# Sheet2.net
KiCad netlist of a schematic drawn in Altium Designer
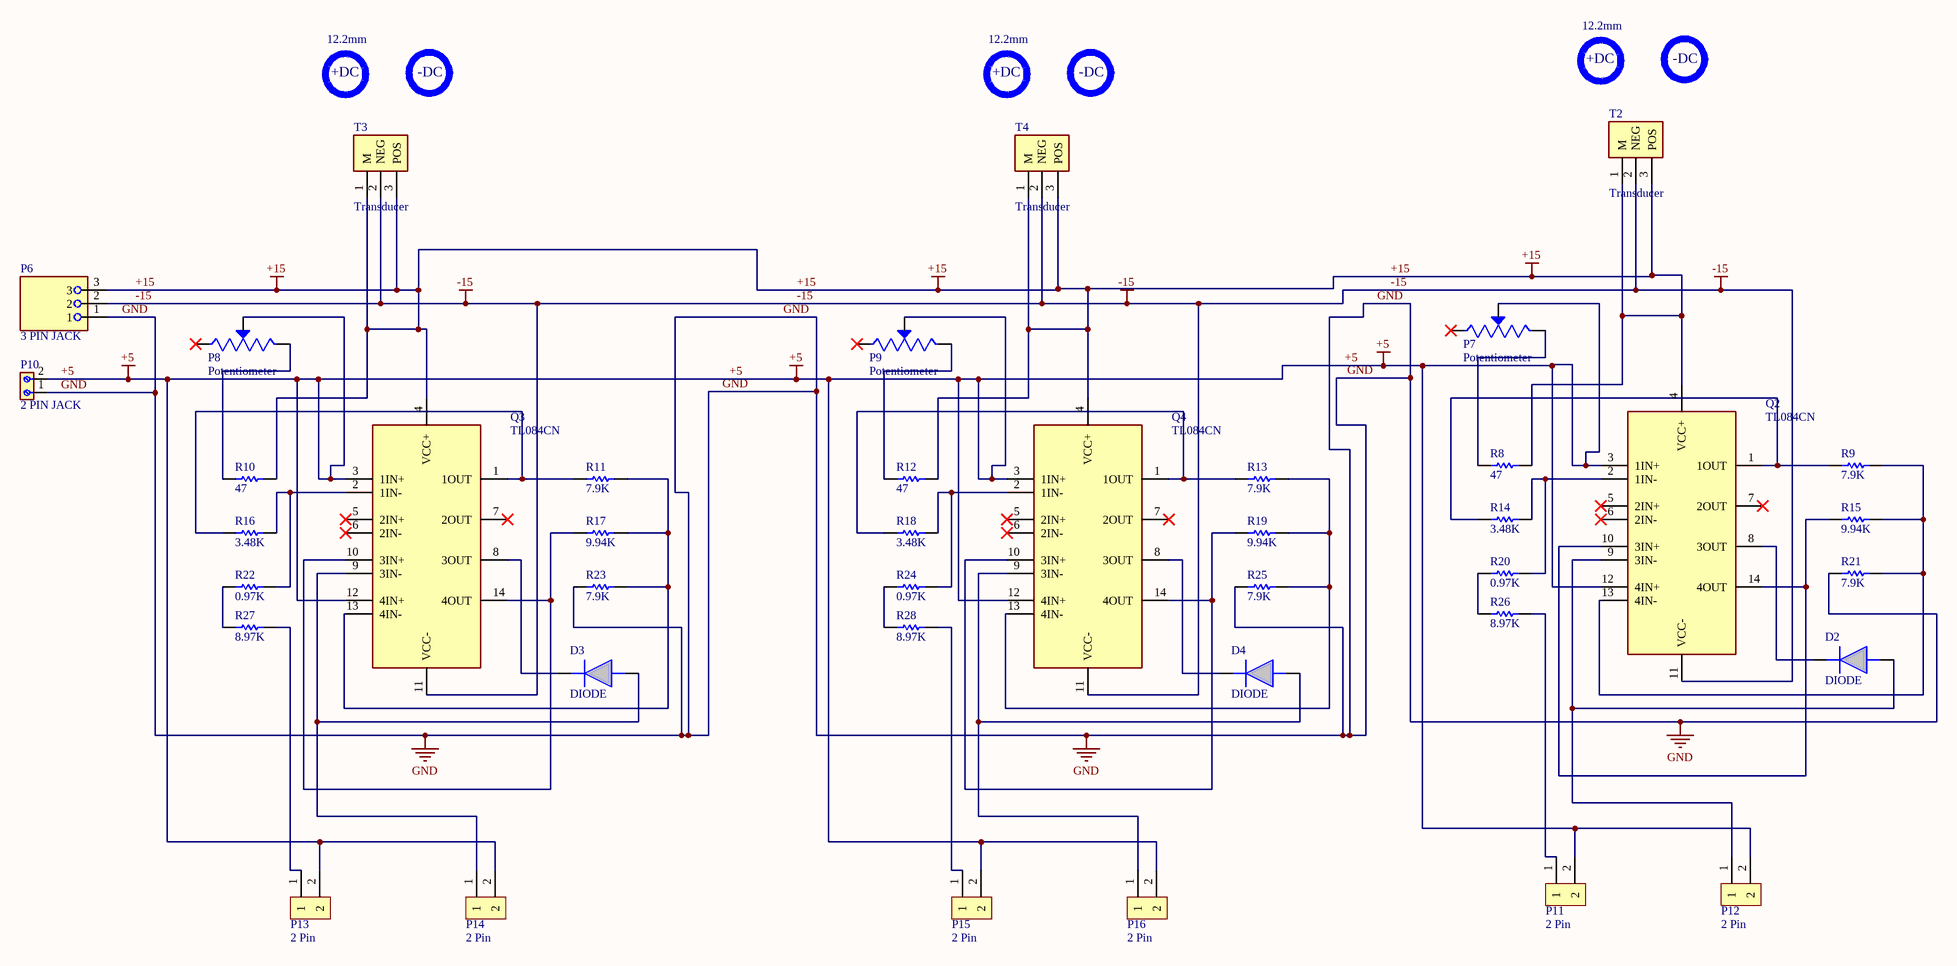
[diagram p0: Sheet2.SchDoc]

(export (version "E")
  (design (tool "Eeschema 10.0.6"))
  (components
    (comp (ref "D2")
      (value "DIODE")
      (footprint "Diode")
      (description "1N4007S")
      (libsource (lib "Schlib1") (part "DIODE"))
    )
    (comp (ref "D3")
      (value "DIODE")
      (footprint "Diode")
      (description "1N4007S")
      (libsource (lib "Schlib1") (part "DIODE"))
    )
    (comp (ref "D4")
      (value "DIODE")
      (footprint "Diode")
      (description "1N4007S")
      (libsource (lib "Schlib1") (part "DIODE"))
    )
    (comp (ref "P6")
      (value "3 PIN JACK")
      (footprint "3 PIN JACK")
      (libsource (lib "Schlib1") (part "3 PIN JACK"))
    )
    (comp (ref "P7")
      (value "Potentiometer")
      (footprint "Potentiometer")
      (libsource (lib "Schlib1") (part "Potentiometer"))
    )
    (comp (ref "P8")
      (value "Potentiometer")
      (footprint "Potentiometer")
      (libsource (lib "Schlib1") (part "Potentiometer"))
    )
    (comp (ref "P9")
      (value "Potentiometer")
      (footprint "Potentiometer")
      (libsource (lib "Schlib1") (part "Potentiometer"))
    )
    (comp (ref "P10")
      (value "2 PIN JACK")
      (footprint "2 PIN JACK")
      (libsource (lib "Schlib1") (part "2 PIN JACK"))
    )
    (comp (ref "P11")
      (value "2 Pin")
      (footprint "2 PIN")
      (description "22272021")
      (libsource (lib "Schlib1") (part "2 Pin"))
    )
    (comp (ref "P12")
      (value "2 Pin")
      (footprint "2 PIN")
      (description "22272021")
      (libsource (lib "Schlib1") (part "2 Pin"))
    )
    (comp (ref "P13")
      (value "2 Pin")
      (footprint "2 PIN")
      (description "22272021")
      (libsource (lib "Schlib1") (part "2 Pin"))
    )
    (comp (ref "P14")
      (value "2 Pin")
      (footprint "2 PIN")
      (description "22272021")
      (libsource (lib "Schlib1") (part "2 Pin"))
    )
    (comp (ref "P15")
      (value "2 Pin")
      (footprint "2 PIN")
      (description "22272021")
      (libsource (lib "Schlib1") (part "2 Pin"))
    )
    (comp (ref "P16")
      (value "2 Pin")
      (footprint "2 PIN")
      (description "22272021")
      (libsource (lib "Schlib1") (part "2 Pin"))
    )
    (comp (ref "Q2") (value "TL084CN") (footprint "TL084CN") (libsource (lib "Schlib1") (part "TL084CN")))
    (comp (ref "Q3") (value "TL084CN") (footprint "TL084CN") (libsource (lib "Schlib1") (part "TL084CN")))
    (comp (ref "Q4") (value "TL084CN") (footprint "TL084CN") (libsource (lib "Schlib1") (part "TL084CN")))
    (comp (ref "R8")
      (value "47")
      (footprint "47")
      (description "MFR-25FRF52-47R")
      (libsource (lib "Schlib1") (part "47"))
    )
    (comp (ref "R9")
      (value "7.9K")
      (footprint "7.90K")
      (description "MFR-25FBF52-7K87")
      (libsource (lib "Schlib1") (part "7.9K"))
    )
    (comp (ref "R10")
      (value "47")
      (footprint "47")
      (description "MFR-25FRF52-47R")
      (libsource (lib "Schlib1") (part "47"))
    )
    (comp (ref "R11")
      (value "7.9K")
      (footprint "7.90K")
      (description "MFR-25FBF52-7K87")
      (libsource (lib "Schlib1") (part "7.9K"))
    )
    (comp (ref "R12")
      (value "47")
      (footprint "47")
      (description "MFR-25FRF52-47R")
      (libsource (lib "Schlib1") (part "47"))
    )
    (comp (ref "R13")
      (value "7.9K")
      (footprint "7.90K")
      (description "MFR-25FBF52-7K87")
      (libsource (lib "Schlib1") (part "7.9K"))
    )
    (comp (ref "R14")
      (value "3.48K")
      (footprint "3.48K")
      (description "MFR-25FBF52-3K48")
      (libsource (lib "Schlib1") (part "3.48K"))
    )
    (comp (ref "R15")
      (value "9.94K")
      (footprint "9.94K")
      (description "MFR-25FTE52-9K76")
      (libsource (lib "Schlib1") (part "9.94K"))
    )
    (comp (ref "R16")
      (value "3.48K")
      (footprint "3.48K")
      (description "MFR-25FBF52-3K48")
      (libsource (lib "Schlib1") (part "3.48K"))
    )
    (comp (ref "R17")
      (value "9.94K")
      (footprint "9.94K")
      (description "MFR-25FTE52-9K76")
      (libsource (lib "Schlib1") (part "9.94K"))
    )
    (comp (ref "R18")
      (value "3.48K")
      (footprint "3.48K")
      (description "MFR-25FBF52-3K48")
      (libsource (lib "Schlib1") (part "3.48K"))
    )
    (comp (ref "R19")
      (value "9.94K")
      (footprint "9.94K")
      (description "MFR-25FTE52-9K76")
      (libsource (lib "Schlib1") (part "9.94K"))
    )
    (comp (ref "R20")
      (value "0.97K")
      (footprint "0.97K")
      (description "MFR-25FRF52-976R")
      (libsource (lib "Schlib1") (part "0.97K"))
    )
    (comp (ref "R21")
      (value "7.9K")
      (footprint "7.90K")
      (description "MFR-25FBF52-7K87")
      (libsource (lib "Schlib1") (part "7.9K"))
    )
    (comp (ref "R22")
      (value "0.97K")
      (footprint "0.97K")
      (description "MFR-25FRF52-976R")
      (libsource (lib "Schlib1") (part "0.97K"))
    )
    (comp (ref "R23")
      (value "7.9K")
      (footprint "7.90K")
      (description "MFR-25FBF52-7K87")
      (libsource (lib "Schlib1") (part "7.9K"))
    )
    (comp (ref "R24")
      (value "0.97K")
      (footprint "0.97K")
      (description "MFR-25FRF52-976R")
      (libsource (lib "Schlib1") (part "0.97K"))
    )
    (comp (ref "R25")
      (value "7.9K")
      (footprint "7.90K")
      (description "MFR-25FBF52-7K87")
      (libsource (lib "Schlib1") (part "7.9K"))
    )
    (comp (ref "R26")
      (value "8.97K")
      (footprint "8.97K")
      (description "MFR-25FBF52-8K87")
      (libsource (lib "Schlib1") (part "8.97K"))
    )
    (comp (ref "R27")
      (value "8.97K")
      (footprint "8.97K")
      (description "MFR-25FBF52-8K87")
      (libsource (lib "Schlib1") (part "8.97K"))
    )
    (comp (ref "R28")
      (value "8.97K")
      (footprint "8.97K")
      (description "MFR-25FBF52-8K87")
      (libsource (lib "Schlib1") (part "8.97K"))
    )
    (comp (ref "T2")
      (value "Transducer")
      (footprint "Transducer")
      (description "LA55-P")
      (libsource (lib "Schlib1") (part "Transducer"))
    )
    (comp (ref "T3")
      (value "Transducer")
      (footprint "Transducer")
      (description "LA55-P")
      (libsource (lib "Schlib1") (part "Transducer"))
    )
    (comp (ref "T4")
      (value "Transducer")
      (footprint "Transducer")
      (description "LA55-P")
      (libsource (lib "Schlib1") (part "Transducer"))
    )
  )
  (nets
    (net (code "1") (name "+5") (class "Default")
      (node (ref "P10") (pin "2") (pinfunction "2_2") (pintype "passive"))
      (node (ref "P11") (pin "2") (pinfunction "2_2") (pintype "passive"))
      (node (ref "P12") (pin "2") (pinfunction "2_2") (pintype "passive"))
      (node (ref "P13") (pin "2") (pinfunction "2_2") (pintype "passive"))
      (node (ref "P14") (pin "2") (pinfunction "2_2") (pintype "passive"))
      (node (ref "P15") (pin "2") (pinfunction "2_2") (pintype "passive"))
      (node (ref "P16") (pin "2") (pinfunction "2_2") (pintype "passive"))
      (node (ref "P7") (pin "2") (pinfunction "WIPER_2") (pintype "passive"))
      (node (ref "P8") (pin "2") (pinfunction "WIPER_2") (pintype "passive"))
      (node (ref "P9") (pin "2") (pinfunction "WIPER_2") (pintype "passive"))
      (node (ref "Q2") (pin "12") (pinfunction "4IN+_12") (pintype "passive"))
      (node (ref "Q2") (pin "3") (pinfunction "1IN+_3") (pintype "passive"))
      (node (ref "Q3") (pin "12") (pinfunction "4IN+_12") (pintype "passive"))
      (node (ref "Q3") (pin "3") (pinfunction "1IN+_3") (pintype "passive"))
      (node (ref "Q4") (pin "12") (pinfunction "4IN+_12") (pintype "passive"))
      (node (ref "Q4") (pin "3") (pinfunction "1IN+_3") (pintype "passive"))
    )
    (net (code "2") (name "+15") (class "Default")
      (node (ref "P6") (pin "3") (pinfunction "3_3") (pintype "passive"))
      (node (ref "Q2") (pin "4") (pinfunction "VCC+_4") (pintype "power_in"))
      (node (ref "Q3") (pin "4") (pinfunction "VCC+_4") (pintype "power_in"))
      (node (ref "Q4") (pin "4") (pinfunction "VCC+_4") (pintype "power_in"))
      (node (ref "R10") (pin "2") (pinfunction "2_2") (pintype "passive"))
      (node (ref "R12") (pin "2") (pinfunction "2_2") (pintype "passive"))
      (node (ref "R8") (pin "2") (pinfunction "2_2") (pintype "passive"))
      (node (ref "T2") (pin "1") (pinfunction "M_1") (pintype "power_in"))
      (node (ref "T2") (pin "3") (pinfunction "POS_3") (pintype "power_in"))
      (node (ref "T3") (pin "1") (pinfunction "M_1") (pintype "power_in"))
      (node (ref "T3") (pin "3") (pinfunction "POS_3") (pintype "power_in"))
      (node (ref "T4") (pin "1") (pinfunction "M_1") (pintype "power_in"))
      (node (ref "T4") (pin "3") (pinfunction "POS_3") (pintype "power_in"))
    )
    (net (code "3") (name "-15") (class "Default")
      (node (ref "P6") (pin "2") (pinfunction "2_2") (pintype "passive"))
      (node (ref "Q2") (pin "11") (pinfunction "VCC-_11") (pintype "power_in"))
      (node (ref "Q3") (pin "11") (pinfunction "VCC-_11") (pintype "power_in"))
      (node (ref "Q4") (pin "11") (pinfunction "VCC-_11") (pintype "power_in"))
      (node (ref "T2") (pin "2") (pinfunction "NEG_2") (pintype "power_in"))
      (node (ref "T3") (pin "2") (pinfunction "NEG_2") (pintype "power_in"))
      (node (ref "T4") (pin "2") (pinfunction "NEG_2") (pintype "power_in"))
    )
    (net (code "4") (name "GND") (class "Default")
      (node (ref "P10") (pin "1") (pinfunction "1_1") (pintype "passive"))
      (node (ref "P6") (pin "1") (pinfunction "1_1") (pintype "passive"))
      (node (ref "R21") (pin "1") (pinfunction "1_1") (pintype "passive"))
      (node (ref "R23") (pin "1") (pinfunction "1_1") (pintype "passive"))
      (node (ref "R25") (pin "1") (pinfunction "1_1") (pintype "passive"))
    )
    (net (code "5") (name "Net-(D2-A)") (class "Default")
      (node (ref "D2") (pin "2") (pinfunction "A_2") (pintype "passive"))
      (node (ref "P12") (pin "1") (pinfunction "1_1") (pintype "passive"))
      (node (ref "Q2") (pin "9") (pinfunction "3IN-_9") (pintype "passive"))
    )
    (net (code "6") (name "Net-(D2-K)") (class "Default")
      (node (ref "D2") (pin "1") (pinfunction "K_1") (pintype "passive"))
      (node (ref "Q2") (pin "8") (pinfunction "3OUT_8") (pintype "passive"))
    )
    (net (code "7") (name "Net-(D3-A)") (class "Default")
      (node (ref "D3") (pin "2") (pinfunction "A_2") (pintype "passive"))
      (node (ref "P14") (pin "1") (pinfunction "1_1") (pintype "passive"))
      (node (ref "Q3") (pin "9") (pinfunction "3IN-_9") (pintype "passive"))
    )
    (net (code "8") (name "Net-(D3-K)") (class "Default")
      (node (ref "D3") (pin "1") (pinfunction "K_1") (pintype "passive"))
      (node (ref "Q3") (pin "8") (pinfunction "3OUT_8") (pintype "passive"))
    )
    (net (code "9") (name "Net-(D4-A)") (class "Default")
      (node (ref "D4") (pin "2") (pinfunction "A_2") (pintype "passive"))
      (node (ref "P16") (pin "1") (pinfunction "1_1") (pintype "passive"))
      (node (ref "Q4") (pin "9") (pinfunction "3IN-_9") (pintype "passive"))
    )
    (net (code "10") (name "Net-(D4-K)") (class "Default")
      (node (ref "D4") (pin "1") (pinfunction "K_1") (pintype "passive"))
      (node (ref "Q4") (pin "8") (pinfunction "3OUT_8") (pintype "passive"))
    )
    (net (code "11") (name "Net-(P7-CW)") (class "Default")
      (node (ref "P7") (pin "3") (pinfunction "CW_3") (pintype "passive"))
      (node (ref "R8") (pin "1") (pinfunction "1_1") (pintype "passive"))
    )
    (net (code "12") (name "Net-(P8-CW)") (class "Default")
      (node (ref "P8") (pin "3") (pinfunction "CW_3") (pintype "passive"))
      (node (ref "R10") (pin "1") (pinfunction "1_1") (pintype "passive"))
    )
    (net (code "13") (name "Net-(P9-CW)") (class "Default")
      (node (ref "P9") (pin "3") (pinfunction "CW_3") (pintype "passive"))
      (node (ref "R12") (pin "1") (pinfunction "1_1") (pintype "passive"))
    )
    (net (code "14") (name "Net-(P11-Pad1)") (class "Default")
      (node (ref "P11") (pin "1") (pinfunction "1_1") (pintype "passive"))
      (node (ref "R26") (pin "2") (pinfunction "2_2") (pintype "passive"))
    )
    (net (code "15") (name "Net-(P13-Pad1)") (class "Default")
      (node (ref "P13") (pin "1") (pinfunction "1_1") (pintype "passive"))
      (node (ref "R27") (pin "2") (pinfunction "2_2") (pintype "passive"))
    )
    (net (code "16") (name "Net-(P15-Pad1)") (class "Default")
      (node (ref "P15") (pin "1") (pinfunction "1_1") (pintype "passive"))
      (node (ref "R28") (pin "2") (pinfunction "2_2") (pintype "passive"))
    )
    (net (code "17") (name "Net-(Q2-1IN-)") (class "Default")
      (node (ref "Q2") (pin "2") (pinfunction "1IN-_2") (pintype "passive"))
      (node (ref "R14") (pin "2") (pinfunction "2_2") (pintype "passive"))
      (node (ref "R20") (pin "2") (pinfunction "2_2") (pintype "passive"))
    )
    (net (code "18") (name "Net-(Q2-1OUT)") (class "Default")
      (node (ref "Q2") (pin "1") (pinfunction "1OUT_1") (pintype "passive"))
      (node (ref "R14") (pin "1") (pinfunction "1_1") (pintype "passive"))
      (node (ref "R9") (pin "1") (pinfunction "1_1") (pintype "passive"))
    )
    (net (code "19") (name "Net-(Q2-3IN+)") (class "Default")
      (node (ref "Q2") (pin "10") (pinfunction "3IN+_10") (pintype "passive"))
      (node (ref "Q2") (pin "14") (pinfunction "4OUT_14") (pintype "passive"))
      (node (ref "R15") (pin "1") (pinfunction "1_1") (pintype "passive"))
    )
    (net (code "20") (name "Net-(Q2-4IN-)") (class "Default")
      (node (ref "Q2") (pin "13") (pinfunction "4IN-_13") (pintype "passive"))
      (node (ref "R15") (pin "2") (pinfunction "2_2") (pintype "passive"))
      (node (ref "R21") (pin "2") (pinfunction "2_2") (pintype "passive"))
      (node (ref "R9") (pin "2") (pinfunction "2_2") (pintype "passive"))
    )
    (net (code "21") (name "Net-(Q3-1IN-)") (class "Default")
      (node (ref "Q3") (pin "2") (pinfunction "1IN-_2") (pintype "passive"))
      (node (ref "R16") (pin "2") (pinfunction "2_2") (pintype "passive"))
      (node (ref "R22") (pin "2") (pinfunction "2_2") (pintype "passive"))
    )
    (net (code "22") (name "Net-(Q3-1OUT)") (class "Default")
      (node (ref "Q3") (pin "1") (pinfunction "1OUT_1") (pintype "passive"))
      (node (ref "R11") (pin "1") (pinfunction "1_1") (pintype "passive"))
      (node (ref "R16") (pin "1") (pinfunction "1_1") (pintype "passive"))
    )
    (net (code "23") (name "Net-(Q3-3IN+)") (class "Default")
      (node (ref "Q3") (pin "10") (pinfunction "3IN+_10") (pintype "passive"))
      (node (ref "Q3") (pin "14") (pinfunction "4OUT_14") (pintype "passive"))
      (node (ref "R17") (pin "1") (pinfunction "1_1") (pintype "passive"))
    )
    (net (code "24") (name "Net-(Q3-4IN-)") (class "Default")
      (node (ref "Q3") (pin "13") (pinfunction "4IN-_13") (pintype "passive"))
      (node (ref "R11") (pin "2") (pinfunction "2_2") (pintype "passive"))
      (node (ref "R17") (pin "2") (pinfunction "2_2") (pintype "passive"))
      (node (ref "R23") (pin "2") (pinfunction "2_2") (pintype "passive"))
    )
    (net (code "25") (name "Net-(Q4-1IN-)") (class "Default")
      (node (ref "Q4") (pin "2") (pinfunction "1IN-_2") (pintype "passive"))
      (node (ref "R18") (pin "2") (pinfunction "2_2") (pintype "passive"))
      (node (ref "R24") (pin "2") (pinfunction "2_2") (pintype "passive"))
    )
    (net (code "26") (name "Net-(Q4-1OUT)") (class "Default")
      (node (ref "Q4") (pin "1") (pinfunction "1OUT_1") (pintype "passive"))
      (node (ref "R13") (pin "1") (pinfunction "1_1") (pintype "passive"))
      (node (ref "R18") (pin "1") (pinfunction "1_1") (pintype "passive"))
    )
    (net (code "27") (name "Net-(Q4-3IN+)") (class "Default")
      (node (ref "Q4") (pin "10") (pinfunction "3IN+_10") (pintype "passive"))
      (node (ref "Q4") (pin "14") (pinfunction "4OUT_14") (pintype "passive"))
      (node (ref "R19") (pin "1") (pinfunction "1_1") (pintype "passive"))
    )
    (net (code "28") (name "Net-(Q4-4IN-)") (class "Default")
      (node (ref "Q4") (pin "13") (pinfunction "4IN-_13") (pintype "passive"))
      (node (ref "R13") (pin "2") (pinfunction "2_2") (pintype "passive"))
      (node (ref "R19") (pin "2") (pinfunction "2_2") (pintype "passive"))
      (node (ref "R25") (pin "2") (pinfunction "2_2") (pintype "passive"))
    )
    (net (code "29") (name "Net-(R20-Pad1)") (class "Default")
      (node (ref "R20") (pin "1") (pinfunction "1_1") (pintype "passive"))
      (node (ref "R26") (pin "1") (pinfunction "1_1") (pintype "passive"))
    )
    (net (code "30") (name "Net-(R22-Pad1)") (class "Default")
      (node (ref "R22") (pin "1") (pinfunction "1_1") (pintype "passive"))
      (node (ref "R27") (pin "1") (pinfunction "1_1") (pintype "passive"))
    )
    (net (code "31") (name "Net-(R24-Pad1)") (class "Default")
      (node (ref "R24") (pin "1") (pinfunction "1_1") (pintype "passive"))
      (node (ref "R28") (pin "1") (pinfunction "1_1") (pintype "passive"))
    )
    (net (code "32") (name "unconnected-(P7-CCW-Pad1)") (class "Default")
      (node (ref "P7") (pin "1") (pinfunction "CCW_1") (pintype "passive+no_connect"))
    )
    (net (code "33") (name "unconnected-(P8-CCW-Pad1)") (class "Default")
      (node (ref "P8") (pin "1") (pinfunction "CCW_1") (pintype "passive+no_connect"))
    )
    (net (code "34") (name "unconnected-(P9-CCW-Pad1)") (class "Default")
      (node (ref "P9") (pin "1") (pinfunction "CCW_1") (pintype "passive+no_connect"))
    )
    (net (code "35") (name "unconnected-(Q2-2IN+-Pad5)") (class "Default")
      (node (ref "Q2") (pin "5") (pinfunction "2IN+_5") (pintype "passive+no_connect"))
    )
    (net (code "36") (name "unconnected-(Q2-2IN--Pad6)") (class "Default")
      (node (ref "Q2") (pin "6") (pinfunction "2IN-_6") (pintype "passive+no_connect"))
    )
    (net (code "37") (name "unconnected-(Q2-2OUT-Pad7)") (class "Default")
      (node (ref "Q2") (pin "7") (pinfunction "2OUT_7") (pintype "passive+no_connect"))
    )
    (net (code "38") (name "unconnected-(Q3-2IN+-Pad5)") (class "Default")
      (node (ref "Q3") (pin "5") (pinfunction "2IN+_5") (pintype "passive+no_connect"))
    )
    (net (code "39") (name "unconnected-(Q3-2IN--Pad6)") (class "Default")
      (node (ref "Q3") (pin "6") (pinfunction "2IN-_6") (pintype "passive+no_connect"))
    )
    (net (code "40") (name "unconnected-(Q3-2OUT-Pad7)") (class "Default")
      (node (ref "Q3") (pin "7") (pinfunction "2OUT_7") (pintype "passive+no_connect"))
    )
    (net (code "41") (name "unconnected-(Q4-2IN+-Pad5)") (class "Default")
      (node (ref "Q4") (pin "5") (pinfunction "2IN+_5") (pintype "passive+no_connect"))
    )
    (net (code "42") (name "unconnected-(Q4-2IN--Pad6)") (class "Default")
      (node (ref "Q4") (pin "6") (pinfunction "2IN-_6") (pintype "passive+no_connect"))
    )
    (net (code "43") (name "unconnected-(Q4-2OUT-Pad7)") (class "Default")
      (node (ref "Q4") (pin "7") (pinfunction "2OUT_7") (pintype "passive+no_connect"))
    )
  )
)
